# 05_-_RTC.net
KiCad netlist of a schematic drawn in Altium Designer
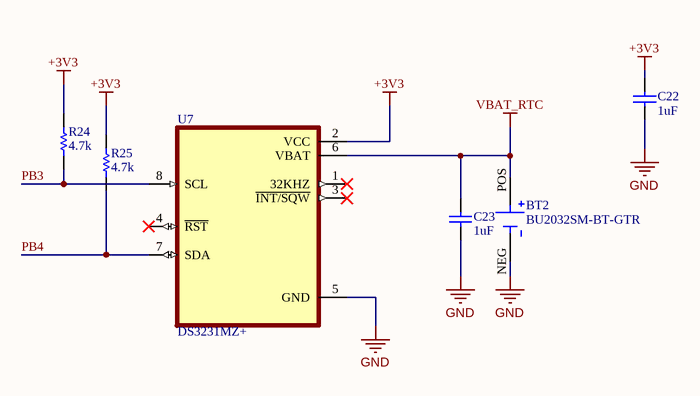
[diagram p0: [05] - RTC.SchDoc]

(export (version "E")
  (design (tool "Eeschema 10.0.6"))
  (components
    (comp (ref "BT2")
      (value "BU2032SM-BT-GTR")
      (footprint "BAT_BU2032SM-BT-GTR")
      (description "Battery Holder (Open) Coin, 20.0mm 1 Cell SMD (SMT) Tab")
      (fields (field (name "MF") "Memory Protection Devices"))
      (libsource (lib "BU2032SM-BT-GTR") (part "BU2032SM-BT-GTR"))
    )
    (comp (ref "C22")
      (value "1uF")
      (footprint "CAP_0603")
      (description "CAP, size 0603, 1uF")
      (libsource (lib "SMIOT_Lib_Schematic") (part "01060310510"))
    )
    (comp (ref "C23")
      (value "1uF")
      (footprint "CAP_0603")
      (description "CAP, size 0603, 1uF")
      (libsource (lib "SMIOT_Lib_Schematic") (part "01060310510"))
    )
    (comp (ref "R24")
      (value "4.7k")
      (footprint "resistor_0603")
      (description "RES, 4.7k Ohm, size 0603, 1%")
      (libsource (lib "SMIOT_Lib_Schematic") (part "0006031031"))
    )
    (comp (ref "R25")
      (value "4.7k")
      (footprint "resistor_0603")
      (description "RES, 4.7k Ohm, size 0603, 1%")
      (libsource (lib "SMIOT_Lib_Schematic") (part "0006031031"))
    )
    (comp (ref "U7")
      (value "DS3231MZ+")
      (footprint "SOIC127P600X175-8N")
      (description "Â±5ppm, I2C Real-Time Clock")
      (fields (field (name "MF") "Analog Devices"))
      (libsource (lib "DS3231MZ_") (part "DS3231MZ+"))
    )
  )
  (nets
    (net (code "1") (name "+3V3") (class "Default")
      (node (ref "C22") (pin "2") (pinfunction "2_2") (pintype "passive"))
      (node (ref "R24") (pin "1") (pinfunction "1_1") (pintype "passive"))
      (node (ref "R25") (pin "1") (pinfunction "1_1") (pintype "passive"))
      (node (ref "U7") (pin "2") (pinfunction "VCC_2") (pintype "power_in"))
    )
    (net (code "2") (name "/PB3") (class "Default")
      (node (ref "R24") (pin "2") (pinfunction "2_2") (pintype "passive"))
      (node (ref "U7") (pin "8") (pinfunction "SCL_8") (pintype "input"))
    )
    (net (code "3") (name "/PB4") (class "Default")
      (node (ref "R25") (pin "2") (pinfunction "2_2") (pintype "passive"))
      (node (ref "U7") (pin "7") (pinfunction "SDA_7") (pintype "bidirectional"))
    )
    (net (code "4") (name "GND") (class "Default")
      (node (ref "BT2") (pin "NEG") (pinfunction "NEG_NEG") (pintype "passive"))
      (node (ref "C22") (pin "1") (pinfunction "1_1") (pintype "passive"))
      (node (ref "C23") (pin "1") (pinfunction "1_1") (pintype "passive"))
      (node (ref "U7") (pin "5") (pinfunction "GND_5") (pintype "power_in"))
    )
    (net (code "5") (name "VBAT_RTC") (class "Default")
      (node (ref "BT2") (pin "POS") (pinfunction "POS_POS") (pintype "passive"))
      (node (ref "C23") (pin "2") (pinfunction "2_2") (pintype "passive"))
      (node (ref "U7") (pin "6") (pinfunction "VBAT_6") (pintype "power_in"))
    )
    (net (code "6") (name "unconnected-(U7-32KHZ-Pad1)") (class "Default")
      (node (ref "U7") (pin "1") (pinfunction "32KHZ_1") (pintype "output+no_connect"))
    )
    (net (code "7") (name "unconnected-(U7-~{INT{slash}SQW}-Pad3)") (class "Default")
      (node (ref "U7") (pin "3") (pinfunction "~{INT/SQW}_3") (pintype "output+no_connect"))
    )
    (net (code "8") (name "unconnected-(U7-~{RST}-Pad4)") (class "Default")
      (node (ref "U7") (pin "4") (pinfunction "~{RST}_4") (pintype "bidirectional+no_connect"))
    )
  )
)
